# PotsDuino.net
KiCad netlist of a schematic drawn in Altium Designer
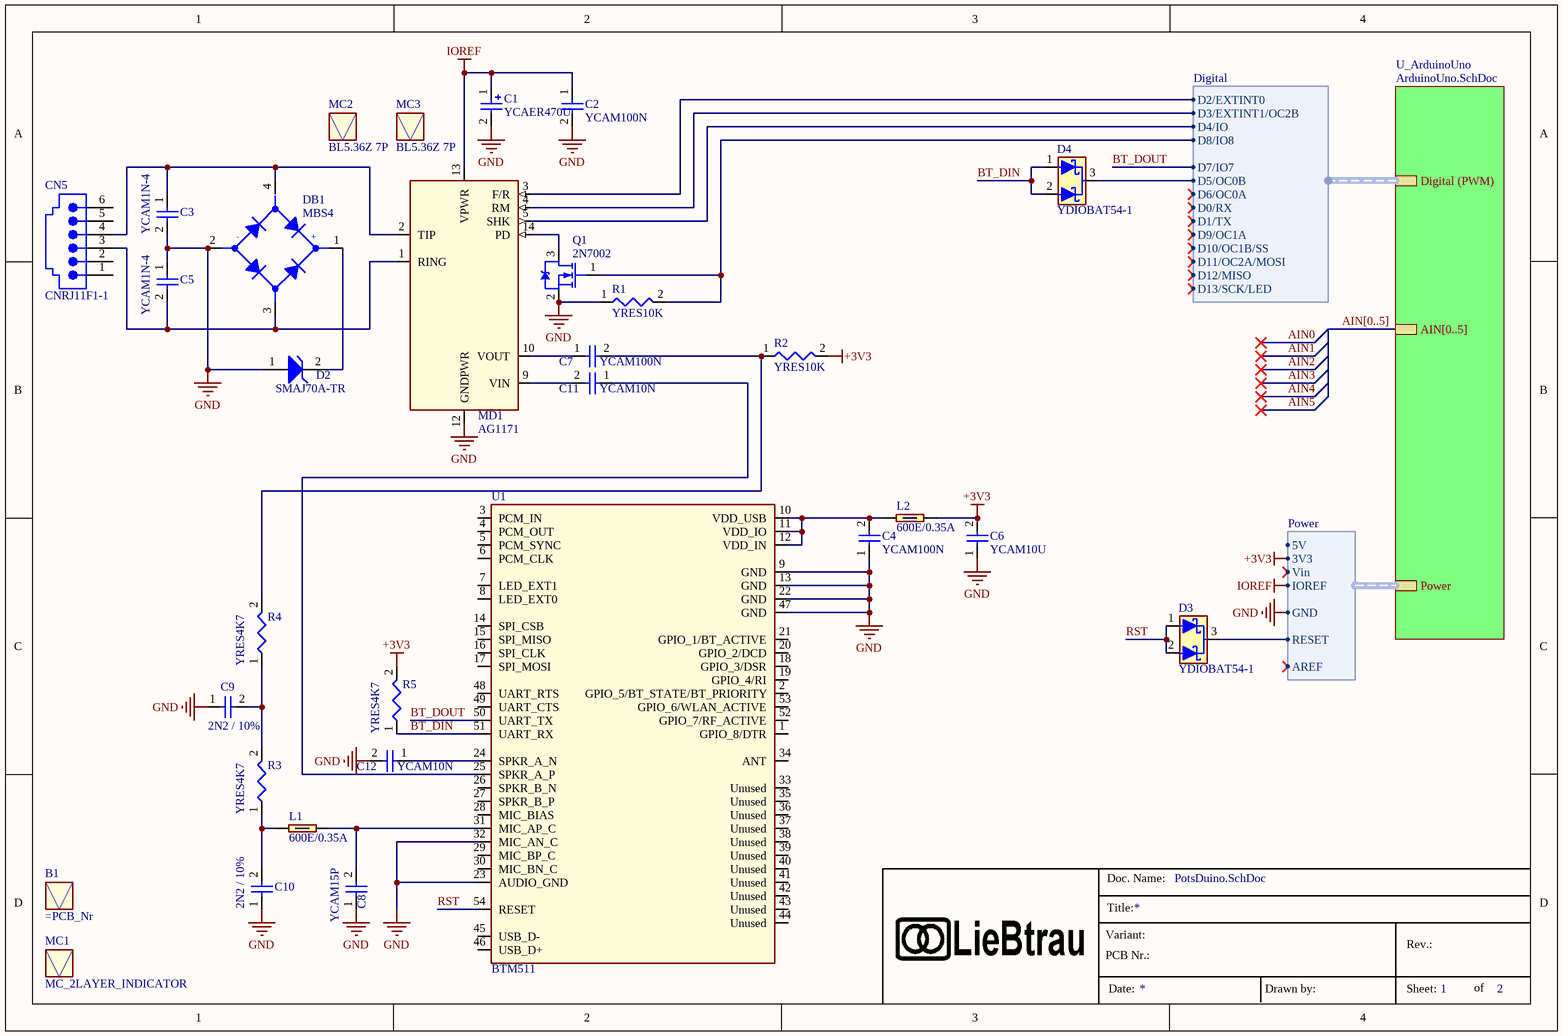
[diagram p0: PotsDuino.SchDoc]

(export (version "E")
  (design (tool "Eeschema 10.0.6"))
  (components
    (comp (ref "B1")
      (value "~")
      (footprint "MC_BoardNr")
      (fields (field (name "PART NUMBER") "BARE_PCB"))
      (libsource (lib "Testing") (part "BD_PCB"))
    )
    (comp (ref "C1")
      (value "YCAER470U")
      (footprint "CA_CANSMD103_H100")
      (fields (field (name "MANUFACTURER") "Panasonic"))
      (libsource (lib "Testing") (part "CA_POL"))
    )
    (comp (ref "C2") (value "YCAM100N") (footprint "CA_1206") (libsource (lib "Testing") (part "CA_NONPOL")))
    (comp (ref "C3")
      (value "YCAM1N-4")
      (footprint "CA_1206")
      (fields (field (name "MANUFACTURER") "AVX"))
      (libsource (lib "Testing") (part "CA_NONPOL"))
    )
    (comp (ref "C4") (value "YCAM100N") (footprint "CA_1206") (libsource (lib "Testing") (part "CA_NONPOL")))
    (comp (ref "C5")
      (value "YCAM1N-4")
      (footprint "CA_1206")
      (fields (field (name "MANUFACTURER") "AVX"))
      (libsource (lib "Testing") (part "CA_NONPOL"))
    )
    (comp (ref "C6") (value "YCAM10U") (footprint "CA_1206") (libsource (lib "Testing") (part "CA_NONPOL")))
    (comp (ref "C7") (value "YCAM100N") (footprint "CA_1206") (libsource (lib "Testing") (part "CA_NONPOL")))
    (comp (ref "C8")
      (value "YCAM15P")
      (footprint "CA_1206")
      (fields (field (name "MANUFACTURER") "Kemet"))
      (libsource (lib "Testing") (part "CA_NONPOL"))
    )
    (comp (ref "C9")
      (value "2N2 / 10%")
      (footprint "CA_1206")
      (fields (field (name "PART NUMBER") "MCCA001357") (field (name "MANUFACTURER") "MULTICOMP"))
      (libsource (lib "Testing") (part "CA_NONPOL"))
    )
    (comp (ref "C10")
      (value "2N2 / 10%")
      (footprint "CA_1206")
      (fields (field (name "PART NUMBER") "MCCA001357") (field (name "MANUFACTURER") "MULTICOMP"))
      (libsource (lib "Testing") (part "CA_NONPOL"))
    )
    (comp (ref "C11")
      (value "YCAM10N")
      (footprint "CA_1206")
      (fields (field (name "MANUFACTURER") "Multicomp"))
      (libsource (lib "Testing") (part "CA_NONPOL"))
    )
    (comp (ref "C12")
      (value "YCAM10N")
      (footprint "CA_1206")
      (fields (field (name "MANUFACTURER") "Multicomp"))
      (libsource (lib "Testing") (part "CA_NONPOL"))
    )
    (comp (ref "CN5")
      (value "CNRJ11F1-1")
      (footprint "CN_MODJACK_6P")
      (libsource (lib "Testing") (part "CN_MODJACK_6P"))
    )
    (comp (ref "D2")
      (value "SMAJ70A-TR")
      (footprint "DI_DO-214AC")
      (fields (field (name "MANUFACTURER") "STMICROELECTRONICS"))
      (libsource (lib "Testing") (part "DI_ZENER"))
    )
    (comp (ref "D3")
      (value "YDIOBAT54-1")
      (footprint "SC_SOT23")
      (description "Dual Schottky Barrier Diode Common Cathode")
      (fields (field (name "MANUFACTURER") "Fairchild Semiconductor"))
      (libsource (lib "Testing") (part "DI_SCHOTTKY_2_CC"))
    )
    (comp (ref "D4")
      (value "YDIOBAT54-1")
      (footprint "SC_SOT23")
      (description "Dual Schottky Barrier Diode Common Cathode")
      (fields (field (name "MANUFACTURER") "Fairchild Semiconductor"))
      (libsource (lib "Testing") (part "DI_SCHOTTKY_2_CC"))
    )
    (comp (ref "DB1")
      (value "MBS4")
      (footprint "SC_SO4")
      (fields (field (name "MANUFACTURER") "TAIWAN SEMICONDUCTOR"))
      (libsource (lib "Testing") (part "DB_BRIDGE-RECT"))
    )
    (comp (ref "L1")
      (value "600E/0.35A")
      (footprint "CL_1206")
      (description "Ferrite Bead")
      (fields (field (name "PART NUMBER") "2512066017Y0") (field (name "MANUFACTURER") "FAIR-RITE"))
      (libsource (lib "Testing") (part "CL_STD_FERRITE"))
    )
    (comp (ref "L2")
      (value "600E/0.35A")
      (footprint "CL_1206")
      (description "Ferrite Bead")
      (fields (field (name "PART NUMBER") "2512066017Y0") (field (name "MANUFACTURER") "FAIR-RITE"))
      (libsource (lib "Testing") (part "CL_STD_FERRITE"))
    )
    (comp (ref "MC1")
      (value "MC_2LAYER_INDICATOR")
      (footprint "MC_2LAYER_INDICATOR")
      (libsource (lib "Testing") (part "MC_MechPart_No_BOM"))
    )
    (comp (ref "MC2")
      (value "BL5.36Z 7P")
      (footprint "CN_TOP_ENTRY_SOCKET_7P_NOHOLES")
      (fields
        (field (name "PART NUMBER") "BL5.36Z 7P MECH")
        (field (name "MANUFACTURER") "Fischer Elektronik")
      )
      (libsource (lib "Testing") (part "MC_MechPart"))
    )
    (comp (ref "MC3")
      (value "BL5.36Z 7P")
      (footprint "CN_TOP_ENTRY_SOCKET_7P_NOHOLES")
      (fields
        (field (name "PART NUMBER") "BL5.36Z 7P MECH")
        (field (name "MANUFACTURER") "Fischer Elektronik")
      )
      (libsource (lib "Testing") (part "MC_MechPart"))
    )
    (comp (ref "MD1")
      (value "AG1171")
      (footprint "MD_AG1171")
      (fields (field (name "MANUFACTURER") "Silvertel"))
      (libsource (lib "Testing") (part "MD_AG1171"))
    )
    (comp (ref "Q1") (value "2N7002") (footprint "SC_SOT23") (libsource (lib "Testing") (part "TR_NMOS")))
    (comp (ref "R1")
      (value "YRES10K")
      (footprint "RE_1206")
      (description "Resistor")
      (fields (field (name "MANUFACTURER") "Vishay Draloric"))
      (libsource (lib "Testing") (part "RE_RES"))
    )
    (comp (ref "R2")
      (value "YRES10K")
      (footprint "RE_1206")
      (description "Resistor")
      (fields (field (name "MANUFACTURER") "Vishay Draloric"))
      (libsource (lib "Testing") (part "RE_RES"))
    )
    (comp (ref "R3")
      (value "YRES4K7")
      (footprint "RE_1206")
      (description "Resistor")
      (fields (field (name "MANUFACTURER") "Vishay Draloric"))
      (libsource (lib "Testing") (part "RE_RES"))
    )
    (comp (ref "R4")
      (value "YRES4K7")
      (footprint "RE_1206")
      (description "Resistor")
      (fields (field (name "MANUFACTURER") "Vishay Draloric"))
      (libsource (lib "Testing") (part "RE_RES"))
    )
    (comp (ref "R5")
      (value "YRES4K7")
      (footprint "RE_1206")
      (description "Resistor")
      (fields (field (name "MANUFACTURER") "Vishay Draloric"))
      (libsource (lib "Testing") (part "RE_RES"))
    )
    (comp (ref "U1")
      (value "BTM511")
      (footprint "SC_BTM511_BOTTOM_UP")
      (fields (field (name "MANUFACTURER") "Laird Technologies"))
      (libsource (lib "Testing") (part "IC_BTM51x"))
    )
  )
  (nets
    (net (code "3") (name "+3V3") (class "Default")
      (node (ref "C6") (pin "2") (pinfunction "2_2") (pintype "passive"))
      (node (ref "L2") (pin "2") (pinfunction "2_2") (pintype "passive"))
      (node (ref "R2") (pin "2") (pinfunction "2_2") (pintype "passive"))
      (node (ref "R5") (pin "2") (pinfunction "2_2") (pintype "passive"))
    )
    (net (code "11") (name "/BT_DIN") (class "Default")
      (node (ref "D4") (pin "1") (pinfunction "A1_1") (pintype "passive"))
      (node (ref "D4") (pin "2") (pinfunction "A2_2") (pintype "passive"))
      (node (ref "R5") (pin "1") (pinfunction "1_1") (pintype "passive"))
      (node (ref "U1") (pin "51") (pinfunction "UART_RX_51") (pintype "passive"))
    )
    (net (code "12") (name "/BT_DOUT") (class "Default")
      (node (ref "U1") (pin "50") (pinfunction "UART_TX_50") (pintype "passive"))
    )
    (net (code "13") (name "/D2{slash}EXTINT0") (class "Default")
      (node (ref "MD1") (pin "3") (pinfunction "F/R_3") (pintype "input"))
    )
    (net (code "14") (name "/D3{slash}EXTINT1{slash}OC2B") (class "Default")
      (node (ref "MD1") (pin "4") (pinfunction "RM_4") (pintype "input"))
    )
    (net (code "15") (name "/D4{slash}IO") (class "Default")
      (node (ref "MD1") (pin "5") (pinfunction "SHK_5") (pintype "output"))
    )
    (net (code "16") (name "/D5{slash}OC0B") (class "Default")
      (node (ref "D4") (pin "3") (pinfunction "C_3") (pintype "passive"))
    )
    (net (code "17") (name "/D8{slash}IO8") (class "Default")
      (node (ref "Q1") (pin "1") (pinfunction "G_1") (pintype "passive"))
      (node (ref "R1") (pin "2") (pinfunction "2_2") (pintype "passive"))
    )
    (net (code "18") (name "/RESET") (class "Default")
      (node (ref "D3") (pin "3") (pinfunction "C_3") (pintype "passive"))
    )
    (net (code "19") (name "/RST") (class "Default")
      (node (ref "D3") (pin "1") (pinfunction "A1_1") (pintype "passive"))
      (node (ref "D3") (pin "2") (pinfunction "A2_2") (pintype "passive"))
      (node (ref "U1") (pin "54") (pinfunction "RESET_54") (pintype "passive"))
    )
    (net (code "22") (name "GND") (class "Default")
      (node (ref "C1") (pin "2") (pinfunction "2_2") (pintype "passive"))
      (node (ref "C10") (pin "1") (pinfunction "1_1") (pintype "passive"))
      (node (ref "C12") (pin "2") (pinfunction "2_2") (pintype "passive"))
      (node (ref "C2") (pin "2") (pinfunction "2_2") (pintype "passive"))
      (node (ref "C3") (pin "2") (pinfunction "2_2") (pintype "passive"))
      (node (ref "C4") (pin "1") (pinfunction "1_1") (pintype "passive"))
      (node (ref "C5") (pin "1") (pinfunction "1_1") (pintype "passive"))
      (node (ref "C6") (pin "1") (pinfunction "1_1") (pintype "passive"))
      (node (ref "C8") (pin "1") (pinfunction "1_1") (pintype "passive"))
      (node (ref "C9") (pin "1") (pinfunction "1_1") (pintype "passive"))
      (node (ref "D2") (pin "1") (pinfunction "A_1") (pintype "passive"))
      (node (ref "DB1") (pin "2") (pinfunction "-DC_2") (pintype "passive"))
      (node (ref "MD1") (pin "12") (pinfunction "GNDPWR_12") (pintype "passive"))
      (node (ref "Q1") (pin "2") (pinfunction "S_2") (pintype "passive"))
      (node (ref "R1") (pin "1") (pinfunction "1_1") (pintype "passive"))
      (node (ref "U1") (pin "13") (pinfunction "GND_13") (pintype "passive"))
      (node (ref "U1") (pin "22") (pinfunction "GND_22") (pintype "passive"))
      (node (ref "U1") (pin "23") (pinfunction "AUDIO_GND_23") (pintype "passive"))
      (node (ref "U1") (pin "32") (pinfunction "MIC_AN_C_32") (pintype "passive"))
      (node (ref "U1") (pin "47") (pinfunction "GND_47") (pintype "passive"))
      (node (ref "U1") (pin "9") (pinfunction "GND_9") (pintype "passive"))
    )
    (net (code "23") (name "IOREF") (class "Default")
      (node (ref "C1") (pin "1") (pinfunction "1_1") (pintype "passive"))
      (node (ref "C2") (pin "1") (pinfunction "1_1") (pintype "passive"))
      (node (ref "MD1") (pin "13") (pinfunction "VPWR_13") (pintype "passive"))
    )
    (net (code "24") (name "Net-(C7-Pad2)") (class "Default")
      (node (ref "C7") (pin "2") (pinfunction "2_2") (pintype "passive"))
      (node (ref "R2") (pin "1") (pinfunction "1_1") (pintype "passive"))
      (node (ref "R4") (pin "2") (pinfunction "2_2") (pintype "passive"))
    )
    (net (code "25") (name "Net-(C9-Pad2)") (class "Default")
      (node (ref "C9") (pin "2") (pinfunction "2_2") (pintype "passive"))
      (node (ref "R3") (pin "2") (pinfunction "2_2") (pintype "passive"))
      (node (ref "R4") (pin "1") (pinfunction "1_1") (pintype "passive"))
    )
    (net (code "26") (name "Net-(C10-Pad2)") (class "Default")
      (node (ref "C10") (pin "2") (pinfunction "2_2") (pintype "passive"))
      (node (ref "L1") (pin "1") (pinfunction "1_1") (pintype "passive"))
      (node (ref "R3") (pin "1") (pinfunction "1_1") (pintype "passive"))
    )
    (net (code "27") (name "Net-(D2-K)") (class "Default")
      (node (ref "D2") (pin "2") (pinfunction "K_2") (pintype "passive"))
      (node (ref "DB1") (pin "1") (pinfunction "+DC_1") (pintype "passive"))
    )
    (net (code "28") (name "Net-(DB1-AC1)") (class "Default")
      (node (ref "C3") (pin "1") (pinfunction "1_1") (pintype "passive"))
      (node (ref "CN5") (pin "4") (pinfunction "4_4") (pintype "passive"))
      (node (ref "DB1") (pin "4") (pinfunction "AC1_4") (pintype "passive"))
      (node (ref "MD1") (pin "2") (pinfunction "TIP_2") (pintype "passive"))
    )
    (net (code "29") (name "Net-(DB1-AC2)") (class "Default")
      (node (ref "C5") (pin "2") (pinfunction "2_2") (pintype "passive"))
      (node (ref "CN5") (pin "3") (pinfunction "3_3") (pintype "passive"))
      (node (ref "DB1") (pin "3") (pinfunction "AC2_3") (pintype "passive"))
      (node (ref "MD1") (pin "1") (pinfunction "RING_1") (pintype "passive"))
    )
    (net (code "30") (name "Net-(MD1-PD)") (class "Default")
      (node (ref "MD1") (pin "14") (pinfunction "PD_14") (pintype "input"))
      (node (ref "Q1") (pin "3") (pinfunction "D_3") (pintype "passive"))
    )
    (net (code "31") (name "Net-(MD1-VIN)") (class "Default")
      (node (ref "C11") (pin "2") (pinfunction "2_2") (pintype "passive"))
      (node (ref "MD1") (pin "9") (pinfunction "VIN_9") (pintype "passive"))
    )
    (net (code "32") (name "Net-(MD1-VOUT)") (class "Default")
      (node (ref "C7") (pin "1") (pinfunction "1_1") (pintype "passive"))
      (node (ref "MD1") (pin "10") (pinfunction "VOUT_10") (pintype "passive"))
    )
    (net (code "33") (name "Net-(U1-MIC_AP_C)") (class "Default")
      (node (ref "C8") (pin "2") (pinfunction "2_2") (pintype "passive"))
      (node (ref "L1") (pin "2") (pinfunction "2_2") (pintype "passive"))
      (node (ref "U1") (pin "31") (pinfunction "MIC_AP_C_31") (pintype "passive"))
    )
    (net (code "34") (name "Net-(U1-SPKR_A_N)") (class "Default")
      (node (ref "C12") (pin "1") (pinfunction "1_1") (pintype "passive"))
      (node (ref "U1") (pin "24") (pinfunction "SPKR_A_N_24") (pintype "passive"))
    )
    (net (code "35") (name "Net-(U1-SPKR_A_P)") (class "Default")
      (node (ref "C11") (pin "1") (pinfunction "1_1") (pintype "passive"))
      (node (ref "U1") (pin "25") (pinfunction "SPKR_A_P_25") (pintype "passive"))
    )
    (net (code "36") (name "Net-(U1-VDD_IN)") (class "Default")
      (node (ref "C4") (pin "2") (pinfunction "2_2") (pintype "passive"))
      (node (ref "L2") (pin "1") (pinfunction "1_1") (pintype "passive"))
      (node (ref "U1") (pin "10") (pinfunction "VDD_USB_10") (pintype "passive"))
      (node (ref "U1") (pin "11") (pinfunction "VDD_IO_11") (pintype "passive"))
      (node (ref "U1") (pin "12") (pinfunction "VDD_IN_12") (pintype "passive"))
    )
    (net (code "37") (name "unconnected-(CN5-Pad1)") (class "Default")
      (node (ref "CN5") (pin "1") (pinfunction "1_1") (pintype "passive"))
    )
    (net (code "38") (name "unconnected-(CN5-Pad2)") (class "Default")
      (node (ref "CN5") (pin "2") (pinfunction "2_2") (pintype "passive"))
    )
    (net (code "39") (name "unconnected-(CN5-Pad5)") (class "Default")
      (node (ref "CN5") (pin "5") (pinfunction "5_5") (pintype "passive"))
    )
    (net (code "40") (name "unconnected-(CN5-Pad6)") (class "Default")
      (node (ref "CN5") (pin "6") (pinfunction "6_6") (pintype "passive"))
    )
    (net (code "41") (name "unconnected-(U1-ANT-Pad34)") (class "Default")
      (node (ref "U1") (pin "34") (pinfunction "ANT_34") (pintype "passive"))
    )
    (net (code "42") (name "unconnected-(U1-GPIO_1{slash}BT_ACTIVE-Pad21)") (class "Default")
      (node (ref "U1") (pin "21") (pinfunction "GPIO_1/BT_ACTIVE_21") (pintype "passive"))
    )
    (net (code "43") (name "unconnected-(U1-GPIO_2{slash}DCD-Pad20)") (class "Default")
      (node (ref "U1") (pin "20") (pinfunction "GPIO_2/DCD_20") (pintype "passive"))
    )
    (net (code "44") (name "unconnected-(U1-GPIO_3{slash}DSR-Pad18)") (class "Default")
      (node (ref "U1") (pin "18") (pinfunction "GPIO_3/DSR_18") (pintype "passive"))
    )
    (net (code "45") (name "unconnected-(U1-GPIO_4{slash}RI-Pad19)") (class "Default")
      (node (ref "U1") (pin "19") (pinfunction "GPIO_4/RI_19") (pintype "passive"))
    )
    (net (code "46") (name "unconnected-(U1-GPIO_5{slash}BT_STATE{slash}BT_PRIORITY-Pad2)") (class "Default")
      (node (ref "U1") (pin "2") (pinfunction "GPIO_5/BT_STATE/BT_PRIORITY_2") (pintype "passive"))
    )
    (net (code "47") (name "unconnected-(U1-GPIO_6{slash}WLAN_ACTIVE-Pad53)") (class "Default")
      (node (ref "U1") (pin "53") (pinfunction "GPIO_6/WLAN_ACTIVE_53") (pintype "passive"))
    )
    (net (code "48") (name "unconnected-(U1-GPIO_7{slash}RF_ACTIVE-Pad52)") (class "Default")
      (node (ref "U1") (pin "52") (pinfunction "GPIO_7/RF_ACTIVE_52") (pintype "passive"))
    )
    (net (code "49") (name "unconnected-(U1-GPIO_8{slash}DTR-Pad1)") (class "Default")
      (node (ref "U1") (pin "1") (pinfunction "GPIO_8/DTR_1") (pintype "passive"))
    )
    (net (code "50") (name "unconnected-(U1-LED_EXT0-Pad8)") (class "Default")
      (node (ref "U1") (pin "8") (pinfunction "LED_EXT0_8") (pintype "passive"))
    )
    (net (code "51") (name "unconnected-(U1-LED_EXT1-Pad7)") (class "Default")
      (node (ref "U1") (pin "7") (pinfunction "LED_EXT1_7") (pintype "passive"))
    )
    (net (code "52") (name "unconnected-(U1-MIC_BIAS-Pad28)") (class "Default")
      (node (ref "U1") (pin "28") (pinfunction "MIC_BIAS_28") (pintype "passive"))
    )
    (net (code "53") (name "unconnected-(U1-MIC_BN_C-Pad30)") (class "Default")
      (node (ref "U1") (pin "30") (pinfunction "MIC_BN_C_30") (pintype "passive"))
    )
    (net (code "54") (name "unconnected-(U1-MIC_BP_C-Pad29)") (class "Default")
      (node (ref "U1") (pin "29") (pinfunction "MIC_BP_C_29") (pintype "passive"))
    )
    (net (code "55") (name "unconnected-(U1-PCM_CLK-Pad6)") (class "Default")
      (node (ref "U1") (pin "6") (pinfunction "PCM_CLK_6") (pintype "passive"))
    )
    (net (code "56") (name "unconnected-(U1-PCM_IN-Pad3)") (class "Default")
      (node (ref "U1") (pin "3") (pinfunction "PCM_IN_3") (pintype "passive"))
    )
    (net (code "57") (name "unconnected-(U1-PCM_OUT-Pad4)") (class "Default")
      (node (ref "U1") (pin "4") (pinfunction "PCM_OUT_4") (pintype "passive"))
    )
    (net (code "58") (name "unconnected-(U1-PCM_SYNC-Pad5)") (class "Default")
      (node (ref "U1") (pin "5") (pinfunction "PCM_SYNC_5") (pintype "passive"))
    )
    (net (code "59") (name "unconnected-(U1-SPI_CLK-Pad16)") (class "Default")
      (node (ref "U1") (pin "16") (pinfunction "SPI_CLK_16") (pintype "passive"))
    )
    (net (code "60") (name "unconnected-(U1-SPI_CSB-Pad14)") (class "Default")
      (node (ref "U1") (pin "14") (pinfunction "SPI_CSB_14") (pintype "passive"))
    )
    (net (code "61") (name "unconnected-(U1-SPI_MISO-Pad15)") (class "Default")
      (node (ref "U1") (pin "15") (pinfunction "SPI_MISO_15") (pintype "passive"))
    )
    (net (code "62") (name "unconnected-(U1-SPI_MOSI-Pad17)") (class "Default")
      (node (ref "U1") (pin "17") (pinfunction "SPI_MOSI_17") (pintype "passive"))
    )
    (net (code "63") (name "unconnected-(U1-SPKR_B_N-Pad26)") (class "Default")
      (node (ref "U1") (pin "26") (pinfunction "SPKR_B_N_26") (pintype "passive"))
    )
    (net (code "64") (name "unconnected-(U1-SPKR_B_P-Pad27)") (class "Default")
      (node (ref "U1") (pin "27") (pinfunction "SPKR_B_P_27") (pintype "passive"))
    )
    (net (code "65") (name "unconnected-(U1-UART_CTS-Pad49)") (class "Default")
      (node (ref "U1") (pin "49") (pinfunction "UART_CTS_49") (pintype "passive"))
    )
    (net (code "66") (name "unconnected-(U1-UART_RTS-Pad48)") (class "Default")
      (node (ref "U1") (pin "48") (pinfunction "UART_RTS_48") (pintype "passive"))
    )
    (net (code "67") (name "unconnected-(U1-USB_D+-Pad46)") (class "Default")
      (node (ref "U1") (pin "46") (pinfunction "USB_D+_46") (pintype "passive"))
    )
    (net (code "68") (name "unconnected-(U1-USB_D--Pad45)") (class "Default")
      (node (ref "U1") (pin "45") (pinfunction "USB_D-_45") (pintype "passive"))
    )
    (net (code "69") (name "unconnected-(U1-Unused-Pad33)") (class "Default")
      (node (ref "U1") (pin "33") (pinfunction "Unused_33") (pintype "passive"))
    )
    (net (code "70") (name "unconnected-(U1-Unused-Pad35)") (class "Default")
      (node (ref "U1") (pin "35") (pinfunction "Unused_35") (pintype "passive"))
    )
    (net (code "71") (name "unconnected-(U1-Unused-Pad36)") (class "Default")
      (node (ref "U1") (pin "36") (pinfunction "Unused_36") (pintype "passive"))
    )
    (net (code "72") (name "unconnected-(U1-Unused-Pad37)") (class "Default")
      (node (ref "U1") (pin "37") (pinfunction "Unused_37") (pintype "passive"))
    )
    (net (code "73") (name "unconnected-(U1-Unused-Pad38)") (class "Default")
      (node (ref "U1") (pin "38") (pinfunction "Unused_38") (pintype "passive"))
    )
    (net (code "74") (name "unconnected-(U1-Unused-Pad39)") (class "Default")
      (node (ref "U1") (pin "39") (pinfunction "Unused_39") (pintype "passive"))
    )
    (net (code "75") (name "unconnected-(U1-Unused-Pad40)") (class "Default")
      (node (ref "U1") (pin "40") (pinfunction "Unused_40") (pintype "passive"))
    )
    (net (code "76") (name "unconnected-(U1-Unused-Pad41)") (class "Default")
      (node (ref "U1") (pin "41") (pinfunction "Unused_41") (pintype "passive"))
    )
    (net (code "77") (name "unconnected-(U1-Unused-Pad42)") (class "Default")
      (node (ref "U1") (pin "42") (pinfunction "Unused_42") (pintype "passive"))
    )
    (net (code "78") (name "unconnected-(U1-Unused-Pad43)") (class "Default")
      (node (ref "U1") (pin "43") (pinfunction "Unused_43") (pintype "passive"))
    )
    (net (code "79") (name "unconnected-(U1-Unused-Pad44)") (class "Default")
      (node (ref "U1") (pin "44") (pinfunction "Unused_44") (pintype "passive"))
    )
  )
)
